# AlarmIn.net
KiCad netlist of a schematic drawn in Altium Designer
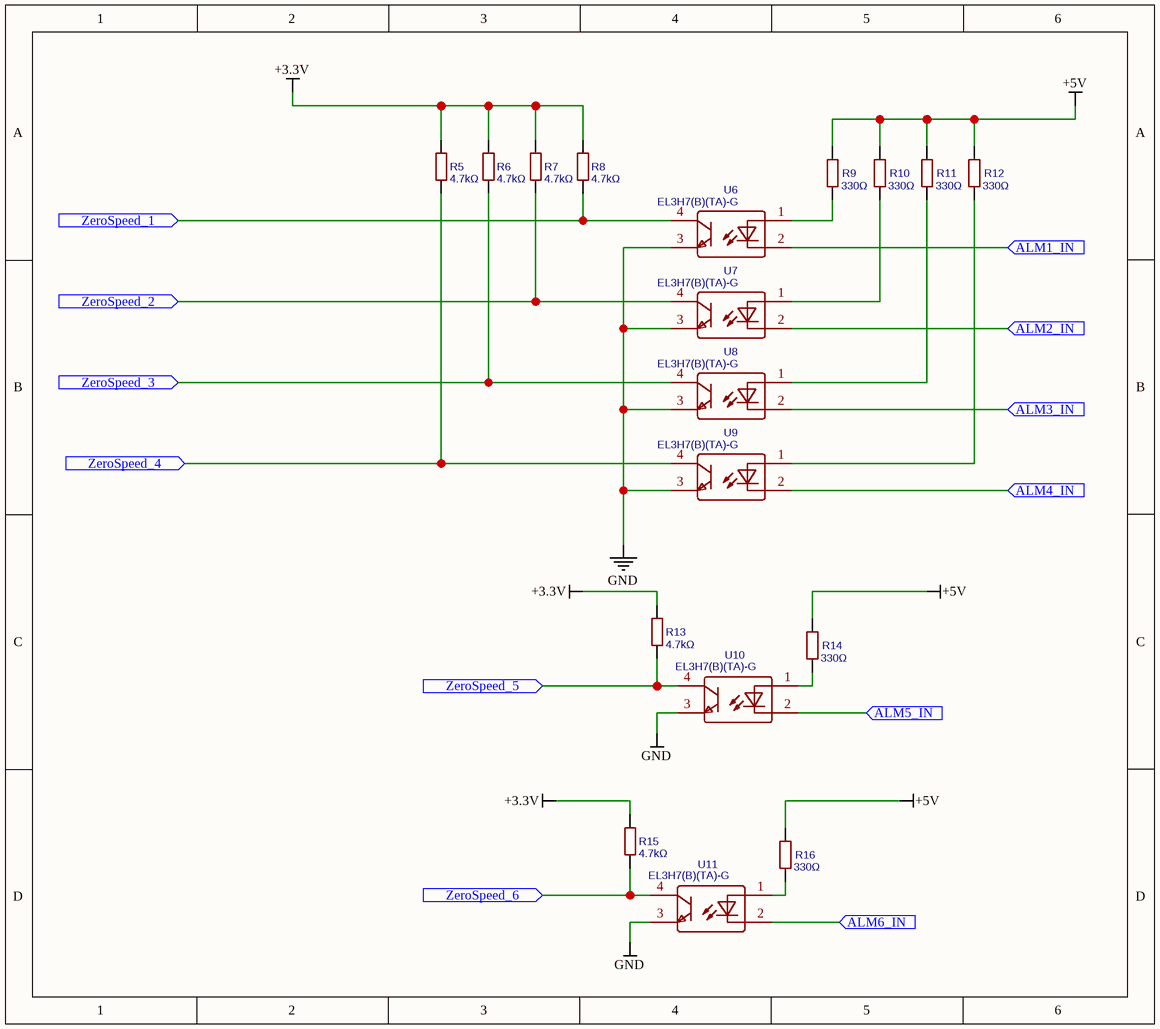
[diagram p0: AlarmIn.schdoc]

(export (version "E")
  (design (tool "Eeschema 10.0.6"))
  (components
    (comp (ref "R5")
      (value "4.7kΩ")
      (fields (field (name "MANUFACTURER") "UniOhm") (field (name "MANUFACTURER PART") "0805W8J0472T5E"))
      (libsource (lib "altium-import") (part "root_1_4.7kΩ_"))
    )
    (comp (ref "R6")
      (value "4.7kΩ")
      (fields (field (name "MANUFACTURER") "UniOhm") (field (name "MANUFACTURER PART") "0805W8J0472T5E"))
      (libsource (lib "altium-import") (part "root_1_4.7kΩ_"))
    )
    (comp (ref "R7")
      (value "4.7kΩ")
      (fields (field (name "MANUFACTURER") "UniOhm") (field (name "MANUFACTURER PART") "0805W8J0472T5E"))
      (libsource (lib "altium-import") (part "root_1_4.7kΩ_"))
    )
    (comp (ref "R8")
      (value "4.7kΩ")
      (fields (field (name "MANUFACTURER") "UniOhm") (field (name "MANUFACTURER PART") "0805W8J0472T5E"))
      (libsource (lib "altium-import") (part "root_1_4.7kΩ_"))
    )
    (comp (ref "R9")
      (value "330Ω")
      (fields
        (field (name "MANUFACTURER") "FH")
        (field (name "MANUFACTURER PART") "RS-03K331FT")
        (field (name "CONTRIBUTOR") "LCSC")
      )
      (libsource (lib "altium-import") (part "root_1_330Ω_"))
    )
    (comp (ref "R10")
      (value "330Ω")
      (fields
        (field (name "MANUFACTURER") "FH")
        (field (name "MANUFACTURER PART") "RS-03K331FT")
        (field (name "CONTRIBUTOR") "LCSC")
      )
      (libsource (lib "altium-import") (part "root_1_330Ω_"))
    )
    (comp (ref "R11")
      (value "330Ω")
      (fields
        (field (name "MANUFACTURER") "FH")
        (field (name "MANUFACTURER PART") "RS-03K331FT")
        (field (name "CONTRIBUTOR") "LCSC")
      )
      (libsource (lib "altium-import") (part "root_1_330Ω_"))
    )
    (comp (ref "R12")
      (value "330Ω")
      (fields
        (field (name "MANUFACTURER") "FH")
        (field (name "MANUFACTURER PART") "RS-03K331FT")
        (field (name "CONTRIBUTOR") "LCSC")
      )
      (libsource (lib "altium-import") (part "root_1_330Ω_"))
    )
    (comp (ref "R13")
      (value "4.7kΩ")
      (fields (field (name "MANUFACTURER") "UniOhm") (field (name "MANUFACTURER PART") "0805W8J0472T5E"))
      (libsource (lib "altium-import") (part "root_1_4.7kΩ_"))
    )
    (comp (ref "R14")
      (value "330Ω")
      (fields
        (field (name "MANUFACTURER") "FH")
        (field (name "MANUFACTURER PART") "RS-03K331FT")
        (field (name "CONTRIBUTOR") "LCSC")
      )
      (libsource (lib "altium-import") (part "root_1_330Ω_"))
    )
    (comp (ref "R15")
      (value "4.7kΩ")
      (fields (field (name "MANUFACTURER") "UniOhm") (field (name "MANUFACTURER PART") "0805W8J0472T5E"))
      (libsource (lib "altium-import") (part "root_1_4.7kΩ_"))
    )
    (comp (ref "R16")
      (value "330Ω")
      (fields
        (field (name "MANUFACTURER") "FH")
        (field (name "MANUFACTURER PART") "RS-03K331FT")
        (field (name "CONTRIBUTOR") "LCSC")
      )
      (libsource (lib "altium-import") (part "root_1_330Ω_"))
    )
    (comp (ref "U6")
      (value "EL3H7(B)(TA)-G")
      (fields (field (name "MANUFACTURER") "EVERLIGHT(亿光)"))
      (libsource (lib "altium-import") (part "root_0_EL3H7(B)(TA)-G_"))
    )
    (comp (ref "U7")
      (value "EL3H7(B)(TA)-G")
      (fields (field (name "MANUFACTURER") "EVERLIGHT(亿光)"))
      (libsource (lib "altium-import") (part "root_0_EL3H7(B)(TA)-G_"))
    )
    (comp (ref "U8")
      (value "EL3H7(B)(TA)-G")
      (fields (field (name "MANUFACTURER") "EVERLIGHT(亿光)"))
      (libsource (lib "altium-import") (part "root_0_EL3H7(B)(TA)-G_"))
    )
    (comp (ref "U9")
      (value "EL3H7(B)(TA)-G")
      (fields (field (name "MANUFACTURER") "EVERLIGHT(亿光)"))
      (libsource (lib "altium-import") (part "root_0_EL3H7(B)(TA)-G_"))
    )
    (comp (ref "U10")
      (value "EL3H7(B)(TA)-G")
      (fields (field (name "MANUFACTURER") "EVERLIGHT(亿光)"))
      (libsource (lib "altium-import") (part "root_0_EL3H7(B)(TA)-G_"))
    )
    (comp (ref "U11")
      (value "EL3H7(B)(TA)-G")
      (fields (field (name "MANUFACTURER") "EVERLIGHT(亿光)"))
      (libsource (lib "altium-import") (part "root_0_EL3H7(B)(TA)-G_"))
    )
  )
  (nets
    (net (code "1") (name "+3.3V") (class "Default")
      (node (ref "R13") (pin "2") (pinfunction "2_2") (pintype "passive"))
      (node (ref "R15") (pin "2") (pinfunction "2_2") (pintype "passive"))
      (node (ref "R5") (pin "2") (pinfunction "2_2") (pintype "passive"))
      (node (ref "R6") (pin "2") (pinfunction "2_2") (pintype "passive"))
      (node (ref "R7") (pin "2") (pinfunction "2_2") (pintype "passive"))
      (node (ref "R8") (pin "2") (pinfunction "2_2") (pintype "passive"))
    )
    (net (code "2") (name "+5V") (class "Default")
      (node (ref "R10") (pin "2") (pinfunction "2_2") (pintype "passive"))
      (node (ref "R11") (pin "2") (pinfunction "2_2") (pintype "passive"))
      (node (ref "R12") (pin "2") (pinfunction "2_2") (pintype "passive"))
      (node (ref "R14") (pin "2") (pinfunction "2_2") (pintype "passive"))
      (node (ref "R16") (pin "2") (pinfunction "2_2") (pintype "passive"))
      (node (ref "R9") (pin "2") (pinfunction "2_2") (pintype "passive"))
    )
    (net (code "3") (name "/ALM1_IN") (class "Default")
      (node (ref "U6") (pin "2") (pinfunction "CAT_2") (pintype "passive"))
    )
    (net (code "4") (name "/ALM2_IN") (class "Default")
      (node (ref "U7") (pin "2") (pinfunction "CAT_2") (pintype "passive"))
    )
    (net (code "5") (name "/ALM3_IN") (class "Default")
      (node (ref "U8") (pin "2") (pinfunction "CAT_2") (pintype "passive"))
    )
    (net (code "6") (name "/ALM4_IN") (class "Default")
      (node (ref "U9") (pin "2") (pinfunction "CAT_2") (pintype "passive"))
    )
    (net (code "7") (name "/ALM5_IN") (class "Default")
      (node (ref "U10") (pin "2") (pinfunction "CAT_2") (pintype "passive"))
    )
    (net (code "8") (name "/ALM6_IN") (class "Default")
      (node (ref "U11") (pin "2") (pinfunction "CAT_2") (pintype "passive"))
    )
    (net (code "9") (name "/ZeroSpeed_1") (class "Default")
      (node (ref "R8") (pin "1") (pinfunction "1_1") (pintype "passive"))
      (node (ref "U6") (pin "4") (pinfunction "COL_4") (pintype "passive"))
    )
    (net (code "10") (name "/ZeroSpeed_2") (class "Default")
      (node (ref "R7") (pin "1") (pinfunction "1_1") (pintype "passive"))
      (node (ref "U7") (pin "4") (pinfunction "COL_4") (pintype "passive"))
    )
    (net (code "11") (name "/ZeroSpeed_3") (class "Default")
      (node (ref "R6") (pin "1") (pinfunction "1_1") (pintype "passive"))
      (node (ref "U8") (pin "4") (pinfunction "COL_4") (pintype "passive"))
    )
    (net (code "12") (name "/ZeroSpeed_4") (class "Default")
      (node (ref "R5") (pin "1") (pinfunction "1_1") (pintype "passive"))
      (node (ref "U9") (pin "4") (pinfunction "COL_4") (pintype "passive"))
    )
    (net (code "13") (name "/ZeroSpeed_5") (class "Default")
      (node (ref "R13") (pin "1") (pinfunction "1_1") (pintype "passive"))
      (node (ref "U10") (pin "4") (pinfunction "COL_4") (pintype "passive"))
    )
    (net (code "14") (name "/ZeroSpeed_6") (class "Default")
      (node (ref "R15") (pin "1") (pinfunction "1_1") (pintype "passive"))
      (node (ref "U11") (pin "4") (pinfunction "COL_4") (pintype "passive"))
    )
    (net (code "15") (name "GND") (class "Default")
      (node (ref "U10") (pin "3") (pinfunction "EM_3") (pintype "passive"))
      (node (ref "U11") (pin "3") (pinfunction "EM_3") (pintype "passive"))
      (node (ref "U6") (pin "3") (pinfunction "EM_3") (pintype "passive"))
      (node (ref "U7") (pin "3") (pinfunction "EM_3") (pintype "passive"))
      (node (ref "U8") (pin "3") (pinfunction "EM_3") (pintype "passive"))
      (node (ref "U9") (pin "3") (pinfunction "EM_3") (pintype "passive"))
    )
    (net (code "16") (name "Net-(U6-AN)") (class "Default")
      (node (ref "R9") (pin "1") (pinfunction "1_1") (pintype "passive"))
      (node (ref "U6") (pin "1") (pinfunction "AN_1") (pintype "passive"))
    )
    (net (code "17") (name "Net-(U7-AN)") (class "Default")
      (node (ref "R10") (pin "1") (pinfunction "1_1") (pintype "passive"))
      (node (ref "U7") (pin "1") (pinfunction "AN_1") (pintype "passive"))
    )
    (net (code "18") (name "Net-(U8-AN)") (class "Default")
      (node (ref "R11") (pin "1") (pinfunction "1_1") (pintype "passive"))
      (node (ref "U8") (pin "1") (pinfunction "AN_1") (pintype "passive"))
    )
    (net (code "19") (name "Net-(U9-AN)") (class "Default")
      (node (ref "R12") (pin "1") (pinfunction "1_1") (pintype "passive"))
      (node (ref "U9") (pin "1") (pinfunction "AN_1") (pintype "passive"))
    )
    (net (code "20") (name "Net-(U10-AN)") (class "Default")
      (node (ref "R14") (pin "1") (pinfunction "1_1") (pintype "passive"))
      (node (ref "U10") (pin "1") (pinfunction "AN_1") (pintype "passive"))
    )
    (net (code "21") (name "Net-(U11-AN)") (class "Default")
      (node (ref "R16") (pin "1") (pinfunction "1_1") (pintype "passive"))
      (node (ref "U11") (pin "1") (pinfunction "AN_1") (pintype "passive"))
    )
  )
)
